# Micromouse_controller_v006.net
KiCad netlist of a schematic drawn in EAGLE
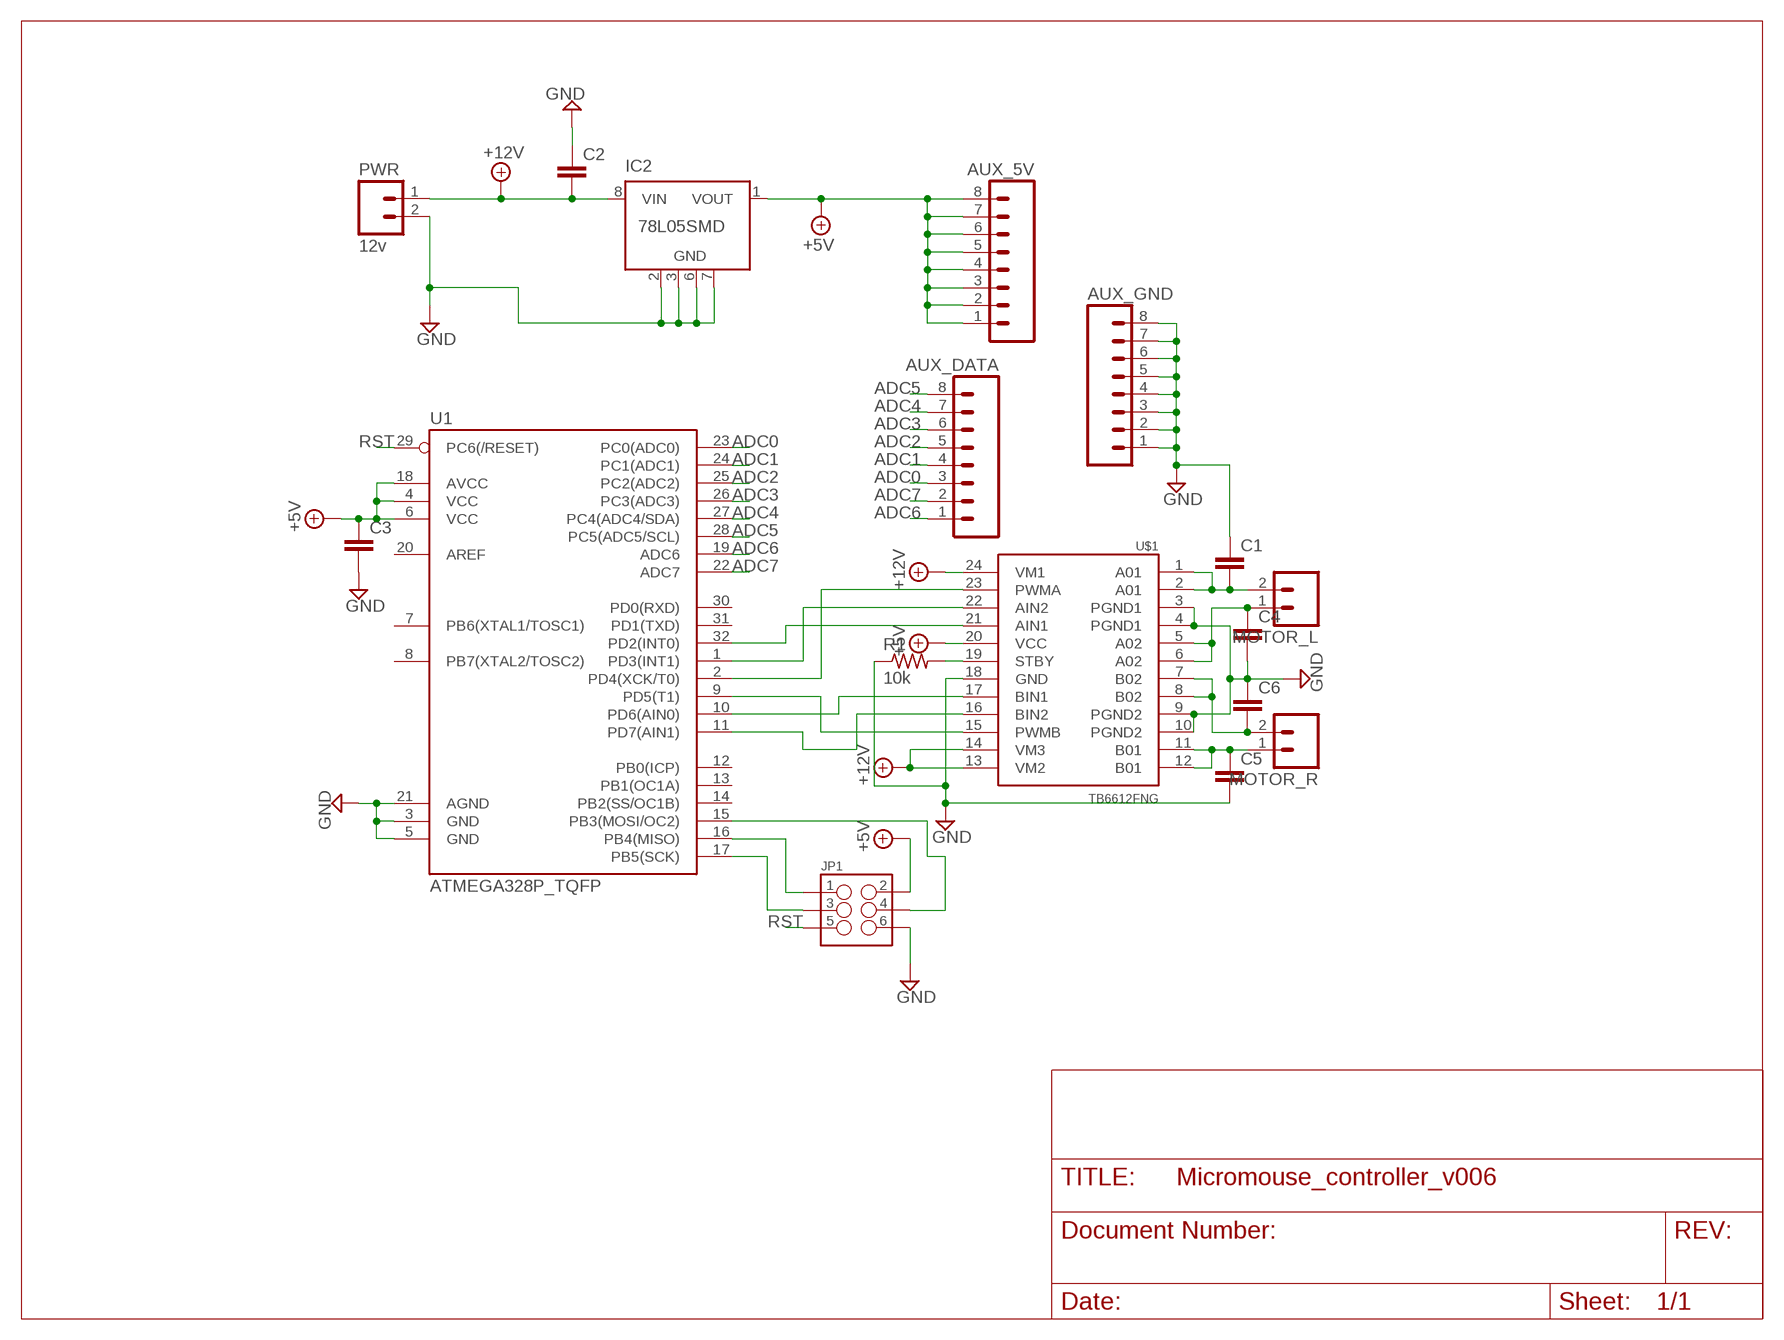
[diagram p0: schematic, sheet 1]

(export (version "E")
  (design (tool "Eeschema 10.0.6"))
  (components
    (comp (ref "AUX_5V")
      (value "M08SMD-STRAIGHT-ALT-FEMALE")
      (footprint "eagle-import:1X08_SMD_ALT")
      (libsource (lib "eagle-import") (part "M08SMD-STRAIGHT-ALT-FEMALE"))
    )
    (comp (ref "AUX_DATA")
      (value "M08SMD-STRAIGHT-ALT-FEMALE")
      (footprint "eagle-import:1X08_SMD_ALT")
      (libsource (lib "eagle-import") (part "M08SMD-STRAIGHT-ALT-FEMALE"))
    )
    (comp (ref "AUX_GND")
      (value "M08SMD-STRAIGHT-ALT-FEMALE")
      (footprint "eagle-import:1X08_SMD_ALT")
      (libsource (lib "eagle-import") (part "M08SMD-STRAIGHT-ALT-FEMALE"))
    )
    (comp (ref "C1")
      (value "CAPSMD")
      (footprint "eagle-import:GRM43D")
      (libsource (lib "eagle-import") (part "CAPSMD"))
    )
    (comp (ref "C2")
      (value "CAPSMD")
      (footprint "eagle-import:GRM43D")
      (libsource (lib "eagle-import") (part "CAPSMD"))
    )
    (comp (ref "C3")
      (value "CAPSMD")
      (footprint "eagle-import:GRM43D")
      (libsource (lib "eagle-import") (part "CAPSMD"))
    )
    (comp (ref "C4")
      (value "CAPSMD")
      (footprint "eagle-import:GRM43D")
      (libsource (lib "eagle-import") (part "CAPSMD"))
    )
    (comp (ref "C5")
      (value "CAPSMD")
      (footprint "eagle-import:GRM43D")
      (libsource (lib "eagle-import") (part "CAPSMD"))
    )
    (comp (ref "C6")
      (value "CAPSMD")
      (footprint "eagle-import:GRM43D")
      (libsource (lib "eagle-import") (part "CAPSMD"))
    )
    (comp (ref "IC2")
      (value "78L05SMD")
      (footprint "eagle-import:SO08")
      (libsource (lib "eagle-import") (part "78LSMD05"))
    )
    (comp (ref "JP1")
      (value "M03X2FEMALE_SMD")
      (footprint "eagle-import:2X3_SMD")
      (libsource (lib "eagle-import") (part "M03X2FEMALE_SMD"))
    )
    (comp (ref "MOTOR_L")
      (value "M02-JST-2MM-SMT")
      (footprint "eagle-import:JST-2-SMD")
      (libsource (lib "eagle-import") (part "M02-JST-2MM-SMT"))
    )
    (comp (ref "MOTOR_R")
      (value "M02-JST-2MM-SMT")
      (footprint "eagle-import:JST-2-SMD")
      (libsource (lib "eagle-import") (part "M02-JST-2MM-SMT"))
    )
    (comp (ref "PWR")
      (value "12v")
      (footprint "eagle-import:JST-2-SMD")
      (libsource (lib "eagle-import") (part "M02-JST-2MM-SMT"))
    )
    (comp (ref "R1")
      (value "10k")
      (footprint "eagle-import:R0603")
      (libsource (lib "eagle-import") (part "R-US_R0603"))
    )
    (comp (ref "U$1")
      (value "TB6612FNG")
      (footprint "eagle-import:SSOP24")
      (libsource (lib "eagle-import") (part "TB6612FNG"))
    )
    (comp (ref "U1")
      (value "ATMEGA328P_TQFP")
      (footprint "eagle-import:TQFP32-08")
      (libsource (lib "eagle-import") (part "ATMEGA328P_TQFP"))
    )
  )
  (nets
    (net (code "1") (name "+5V") (class "Default")
      (node (ref "AUX_5V") (pin "1") (pinfunction "1_1") (pintype "passive"))
      (node (ref "AUX_5V") (pin "2") (pinfunction "2_2") (pintype "passive"))
      (node (ref "AUX_5V") (pin "3") (pinfunction "3_3") (pintype "passive"))
      (node (ref "AUX_5V") (pin "4") (pinfunction "4_4") (pintype "passive"))
      (node (ref "AUX_5V") (pin "5") (pinfunction "5_5") (pintype "passive"))
      (node (ref "AUX_5V") (pin "6") (pinfunction "6_6") (pintype "passive"))
      (node (ref "AUX_5V") (pin "7") (pinfunction "7_7") (pintype "passive"))
      (node (ref "AUX_5V") (pin "8") (pinfunction "8_8") (pintype "passive"))
      (node (ref "C3") (pin "A") (pinfunction "1_A") (pintype "passive"))
      (node (ref "IC2") (pin "1") (pinfunction "VOUT_1") (pintype "output"))
      (node (ref "JP1") (pin "2") (pinfunction "2_2") (pintype "bidirectional"))
      (node (ref "U$1") (pin "20") (pinfunction "VCC_20") (pintype "bidirectional"))
      (node (ref "U1") (pin "18") (pinfunction "AVCC_18") (pintype "bidirectional"))
      (node (ref "U1") (pin "4") (pinfunction "VCC_4") (pintype "bidirectional"))
      (node (ref "U1") (pin "6") (pinfunction "VCC_6") (pintype "bidirectional"))
    )
    (net (code "2") (name "+12V") (class "Default")
      (node (ref "C2") (pin "C") (pinfunction "2_C") (pintype "passive"))
      (node (ref "IC2") (pin "8") (pinfunction "VIN_8") (pintype "passive"))
      (node (ref "PWR") (pin "1") (pinfunction "2_1") (pintype "passive"))
      (node (ref "U$1") (pin "13") (pinfunction "VM2_13") (pintype "bidirectional"))
      (node (ref "U$1") (pin "14") (pinfunction "VM3_14") (pintype "bidirectional"))
      (node (ref "U$1") (pin "24") (pinfunction "VM1_24") (pintype "bidirectional"))
    )
    (net (code "3") (name "/ADC0") (class "Default")
      (node (ref "AUX_DATA") (pin "3") (pinfunction "3_3") (pintype "passive"))
      (node (ref "U1") (pin "23") (pinfunction "PC0(ADC0)_23") (pintype "bidirectional"))
    )
    (net (code "4") (name "/ADC1") (class "Default")
      (node (ref "AUX_DATA") (pin "4") (pinfunction "4_4") (pintype "passive"))
      (node (ref "U1") (pin "24") (pinfunction "PC1(ADC1)_24") (pintype "bidirectional"))
    )
    (net (code "5") (name "/ADC2") (class "Default")
      (node (ref "AUX_DATA") (pin "5") (pinfunction "5_5") (pintype "passive"))
      (node (ref "U1") (pin "25") (pinfunction "PC2(ADC2)_25") (pintype "bidirectional"))
    )
    (net (code "6") (name "/ADC3") (class "Default")
      (node (ref "AUX_DATA") (pin "6") (pinfunction "6_6") (pintype "passive"))
      (node (ref "U1") (pin "26") (pinfunction "PC3(ADC3)_26") (pintype "bidirectional"))
    )
    (net (code "7") (name "/ADC4") (class "Default")
      (node (ref "AUX_DATA") (pin "7") (pinfunction "7_7") (pintype "passive"))
      (node (ref "U1") (pin "27") (pinfunction "PC4(ADC4/SDA)_27") (pintype "bidirectional"))
    )
    (net (code "8") (name "/ADC5") (class "Default")
      (node (ref "AUX_DATA") (pin "8") (pinfunction "8_8") (pintype "passive"))
      (node (ref "U1") (pin "28") (pinfunction "PC5(ADC5/SCL)_28") (pintype "bidirectional"))
    )
    (net (code "9") (name "/ADC6") (class "Default")
      (node (ref "AUX_DATA") (pin "1") (pinfunction "1_1") (pintype "passive"))
      (node (ref "U1") (pin "19") (pinfunction "ADC6_19") (pintype "bidirectional"))
    )
    (net (code "10") (name "/ADC7") (class "Default")
      (node (ref "AUX_DATA") (pin "2") (pinfunction "2_2") (pintype "passive"))
      (node (ref "U1") (pin "22") (pinfunction "ADC7_22") (pintype "bidirectional"))
    )
    (net (code "11") (name "/RST") (class "Default")
      (node (ref "JP1") (pin "5") (pinfunction "5_5") (pintype "bidirectional"))
      (node (ref "U1") (pin "29") (pinfunction "PC6(/RESET)_29") (pintype "bidirectional"))
    )
    (net (code "12") (name "GND") (class "Default")
      (node (ref "AUX_GND") (pin "1") (pinfunction "1_1") (pintype "passive"))
      (node (ref "AUX_GND") (pin "2") (pinfunction "2_2") (pintype "passive"))
      (node (ref "AUX_GND") (pin "3") (pinfunction "3_3") (pintype "passive"))
      (node (ref "AUX_GND") (pin "4") (pinfunction "4_4") (pintype "passive"))
      (node (ref "AUX_GND") (pin "5") (pinfunction "5_5") (pintype "passive"))
      (node (ref "AUX_GND") (pin "6") (pinfunction "6_6") (pintype "passive"))
      (node (ref "AUX_GND") (pin "7") (pinfunction "7_7") (pintype "passive"))
      (node (ref "AUX_GND") (pin "8") (pinfunction "8_8") (pintype "passive"))
      (node (ref "C1") (pin "A") (pinfunction "1_A") (pintype "passive"))
      (node (ref "C2") (pin "A") (pinfunction "1_A") (pintype "passive"))
      (node (ref "C3") (pin "C") (pinfunction "2_C") (pintype "passive"))
      (node (ref "C4") (pin "C") (pinfunction "2_C") (pintype "passive"))
      (node (ref "C5") (pin "C") (pinfunction "2_C") (pintype "passive"))
      (node (ref "C6") (pin "A") (pinfunction "1_A") (pintype "passive"))
      (node (ref "IC2") (pin "2") (pinfunction "GND_2") (pintype "power_in"))
      (node (ref "IC2") (pin "3") (pinfunction "GND_3") (pintype "power_in"))
      (node (ref "IC2") (pin "6") (pinfunction "GND_6") (pintype "power_in"))
      (node (ref "IC2") (pin "7") (pinfunction "GND_7") (pintype "power_in"))
      (node (ref "JP1") (pin "6") (pinfunction "6_6") (pintype "bidirectional"))
      (node (ref "PWR") (pin "2") (pinfunction "1_2") (pintype "passive"))
      (node (ref "R1") (pin "1") (pinfunction "1_1") (pintype "passive"))
      (node (ref "U$1") (pin "10") (pinfunction "PGND2_10") (pintype "bidirectional"))
      (node (ref "U$1") (pin "18") (pinfunction "GND_18") (pintype "bidirectional"))
      (node (ref "U$1") (pin "3") (pinfunction "PGND1_3") (pintype "bidirectional"))
      (node (ref "U$1") (pin "4") (pinfunction "PGND1_4") (pintype "bidirectional"))
      (node (ref "U$1") (pin "9") (pinfunction "PGND2_9") (pintype "bidirectional"))
      (node (ref "U1") (pin "21") (pinfunction "AGND_21") (pintype "bidirectional"))
      (node (ref "U1") (pin "3") (pinfunction "GND_3") (pintype "bidirectional"))
      (node (ref "U1") (pin "5") (pinfunction "GND_5") (pintype "bidirectional"))
    )
    (net (code "13") (name "Net-(C1-2)") (class "Default")
      (node (ref "C1") (pin "C") (pinfunction "2_C") (pintype "passive"))
      (node (ref "MOTOR_L") (pin "2") (pinfunction "1_2") (pintype "passive"))
      (node (ref "U$1") (pin "1") (pinfunction "A01_1") (pintype "bidirectional"))
      (node (ref "U$1") (pin "2") (pinfunction "A01_2") (pintype "bidirectional"))
    )
    (net (code "14") (name "Net-(C4-1)") (class "Default")
      (node (ref "C4") (pin "A") (pinfunction "1_A") (pintype "passive"))
      (node (ref "MOTOR_L") (pin "1") (pinfunction "2_1") (pintype "passive"))
      (node (ref "U$1") (pin "5") (pinfunction "A02_5") (pintype "bidirectional"))
      (node (ref "U$1") (pin "6") (pinfunction "A02_6") (pintype "bidirectional"))
    )
    (net (code "15") (name "Net-(C5-1)") (class "Default")
      (node (ref "C5") (pin "A") (pinfunction "1_A") (pintype "passive"))
      (node (ref "MOTOR_R") (pin "1") (pinfunction "2_1") (pintype "passive"))
      (node (ref "U$1") (pin "11") (pinfunction "B01_11") (pintype "bidirectional"))
      (node (ref "U$1") (pin "12") (pinfunction "B01_12") (pintype "bidirectional"))
    )
    (net (code "16") (name "Net-(C6-2)") (class "Default")
      (node (ref "C6") (pin "C") (pinfunction "2_C") (pintype "passive"))
      (node (ref "MOTOR_R") (pin "2") (pinfunction "1_2") (pintype "passive"))
      (node (ref "U$1") (pin "7") (pinfunction "B02_7") (pintype "bidirectional"))
      (node (ref "U$1") (pin "8") (pinfunction "B02_8") (pintype "bidirectional"))
    )
    (net (code "17") (name "Net-(U$1-AIN1)") (class "Default")
      (node (ref "U$1") (pin "21") (pinfunction "AIN1_21") (pintype "bidirectional"))
      (node (ref "U1") (pin "32") (pinfunction "PD2(INT0)_32") (pintype "bidirectional"))
    )
    (net (code "18") (name "Net-(U$1-AIN2)") (class "Default")
      (node (ref "U$1") (pin "22") (pinfunction "AIN2_22") (pintype "bidirectional"))
      (node (ref "U1") (pin "1") (pinfunction "PD3(INT1)_1") (pintype "bidirectional"))
    )
    (net (code "19") (name "Net-(U$1-BIN1)") (class "Default")
      (node (ref "U$1") (pin "17") (pinfunction "BIN1_17") (pintype "bidirectional"))
      (node (ref "U1") (pin "10") (pinfunction "PD6(AIN0)_10") (pintype "bidirectional"))
    )
    (net (code "20") (name "Net-(U$1-BIN2)") (class "Default")
      (node (ref "U$1") (pin "16") (pinfunction "BIN2_16") (pintype "bidirectional"))
      (node (ref "U1") (pin "11") (pinfunction "PD7(AIN1)_11") (pintype "bidirectional"))
    )
    (net (code "21") (name "Net-(U$1-PWMA)") (class "Default")
      (node (ref "U$1") (pin "23") (pinfunction "PWMA_23") (pintype "bidirectional"))
      (node (ref "U1") (pin "2") (pinfunction "PD4(XCK/T0)_2") (pintype "bidirectional"))
    )
    (net (code "22") (name "Net-(U$1-PWMB)") (class "Default")
      (node (ref "U$1") (pin "15") (pinfunction "PWMB_15") (pintype "bidirectional"))
      (node (ref "U1") (pin "9") (pinfunction "PD5(T1)_9") (pintype "bidirectional"))
    )
    (net (code "23") (name "Net-(U$1-STBY)") (class "Default")
      (node (ref "R1") (pin "2") (pinfunction "2_2") (pintype "passive"))
      (node (ref "U$1") (pin "19") (pinfunction "STBY_19") (pintype "bidirectional"))
    )
    (net (code "24") (name "Net-(U1-PB3(MOSI{slash}OC2))") (class "Default")
      (node (ref "JP1") (pin "4") (pinfunction "4_4") (pintype "bidirectional"))
      (node (ref "U1") (pin "15") (pinfunction "PB3(MOSI/OC2)_15") (pintype "bidirectional"))
    )
    (net (code "25") (name "Net-(U1-PB4(MISO))") (class "Default")
      (node (ref "JP1") (pin "1") (pinfunction "1_1") (pintype "bidirectional"))
      (node (ref "U1") (pin "16") (pinfunction "PB4(MISO)_16") (pintype "bidirectional"))
    )
    (net (code "26") (name "Net-(U1-PB5(SCK))") (class "Default")
      (node (ref "JP1") (pin "3") (pinfunction "3_3") (pintype "bidirectional"))
      (node (ref "U1") (pin "17") (pinfunction "PB5(SCK)_17") (pintype "bidirectional"))
    )
    (net (code "27") (name "unconnected-(U1-AREF-Pad20)") (class "Default")
      (node (ref "U1") (pin "20") (pinfunction "AREF_20") (pintype "bidirectional"))
    )
    (net (code "28") (name "unconnected-(U1-PB0(ICP)-Pad12)") (class "Default")
      (node (ref "U1") (pin "12") (pinfunction "PB0(ICP)_12") (pintype "bidirectional"))
    )
    (net (code "29") (name "unconnected-(U1-PB1(OC1A)-Pad13)") (class "Default")
      (node (ref "U1") (pin "13") (pinfunction "PB1(OC1A)_13") (pintype "bidirectional"))
    )
    (net (code "30") (name "unconnected-(U1-PB2(SS{slash}OC1B)-Pad14)") (class "Default")
      (node (ref "U1") (pin "14") (pinfunction "PB2(SS/OC1B)_14") (pintype "bidirectional"))
    )
    (net (code "31") (name "unconnected-(U1-PB6(XTAL1{slash}TOSC1)-Pad7)") (class "Default")
      (node (ref "U1") (pin "7") (pinfunction "PB6(XTAL1/TOSC1)_7") (pintype "bidirectional"))
    )
    (net (code "32") (name "unconnected-(U1-PB7(XTAL2{slash}TOSC2)-Pad8)") (class "Default")
      (node (ref "U1") (pin "8") (pinfunction "PB7(XTAL2/TOSC2)_8") (pintype "bidirectional"))
    )
    (net (code "33") (name "unconnected-(U1-PD0(RXD)-Pad30)") (class "Default")
      (node (ref "U1") (pin "30") (pinfunction "PD0(RXD)_30") (pintype "bidirectional"))
    )
    (net (code "34") (name "unconnected-(U1-PD1(TXD)-Pad31)") (class "Default")
      (node (ref "U1") (pin "31") (pinfunction "PD1(TXD)_31") (pintype "bidirectional"))
    )
  )
)
